# crz7shld.net
KiCad netlist of a schematic drawn in EAGLE
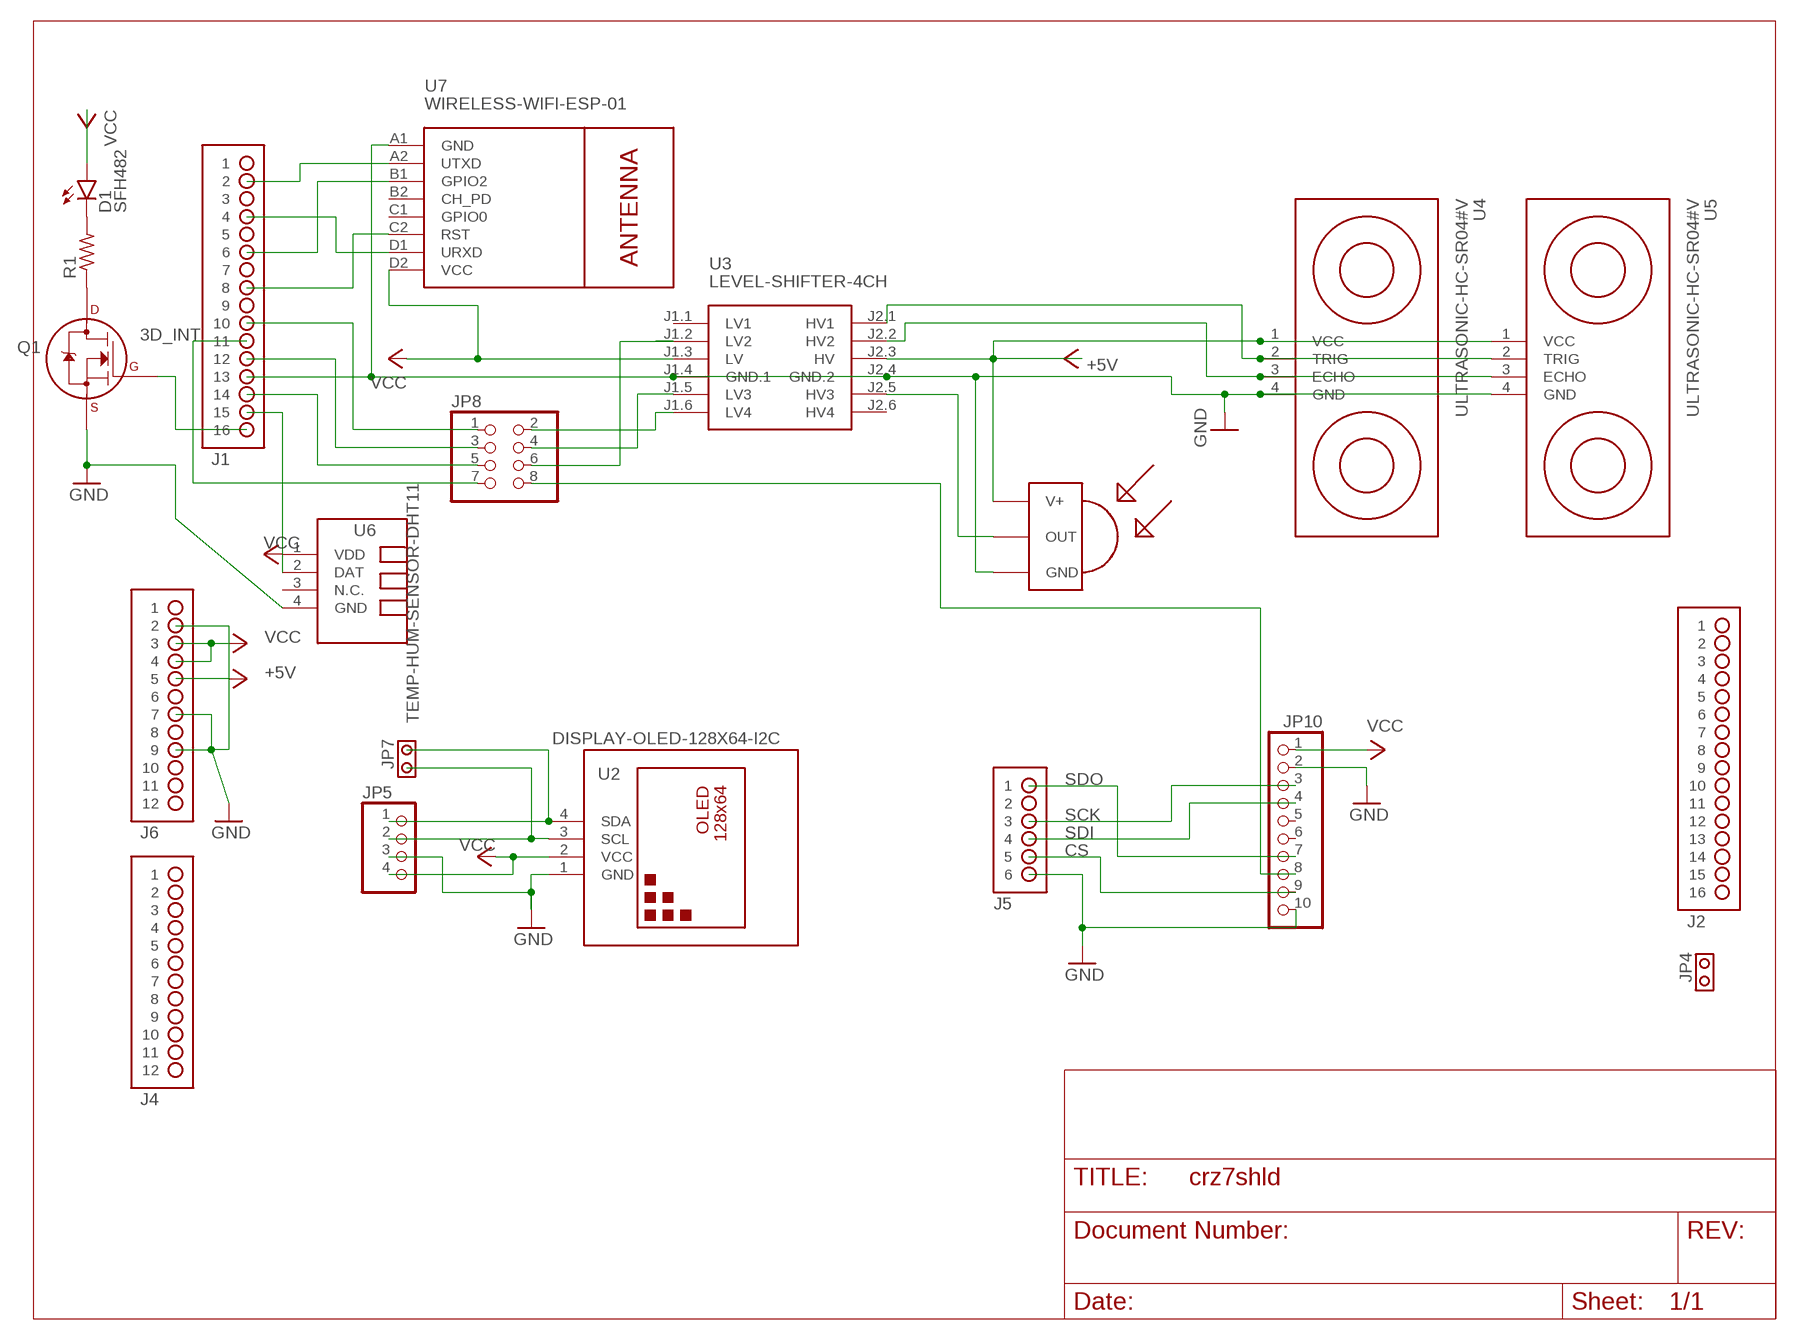
[diagram p0: schematic, sheet 1]

(export (version "E")
  (design (tool "Eeschema 10.0.6"))
  (components
    (comp (ref "D1")
      (value "SFH482")
      (footprint "eagle-import:SFH482")
      (libsource (lib "eagle-import") (part "SFH482"))
    )
    (comp (ref "J1")
      (value "HDR-2X8")
      (footprint "eagle-import:HDR-2X8")
      (libsource (lib "eagle-import") (part "HDR-2X8"))
    )
    (comp (ref "J2")
      (value "HDR-2X8")
      (footprint "eagle-import:HDR-2X8")
      (libsource (lib "eagle-import") (part "HDR-2X8"))
    )
    (comp (ref "J4")
      (value "HDR-2X6")
      (footprint "eagle-import:HDR-2X6")
      (libsource (lib "eagle-import") (part "HDR-2X6"))
    )
    (comp (ref "J5")
      (value "HDR-2X3")
      (footprint "eagle-import:HDR-2X3")
      (libsource (lib "eagle-import") (part "HDR-2X3"))
    )
    (comp (ref "J6")
      (value "HDR-2X6")
      (footprint "eagle-import:HDR-2X6")
      (libsource (lib "eagle-import") (part "HDR-2X6"))
    )
    (comp (ref "JP4")
      (value "JPR-1X2")
      (footprint "eagle-import:JPR-1X2")
      (libsource (lib "eagle-import") (part "JPR-1X2"))
    )
    (comp (ref "JP5")
      (value "PINHD-1X4")
      (footprint "eagle-import:1X04")
      (libsource (lib "eagle-import") (part "PINHD-1X4"))
    )
    (comp (ref "JP7")
      (value "JPR-1X2")
      (footprint "eagle-import:JPR-1X2")
      (libsource (lib "eagle-import") (part "JPR-1X2"))
    )
    (comp (ref "JP8")
      (value "PINHD-2X4")
      (footprint "eagle-import:2X04")
      (libsource (lib "eagle-import") (part "PINHD-2X4"))
    )
    (comp (ref "JP10")
      (value "PINHD-1X10")
      (footprint "eagle-import:1X10")
      (libsource (lib "eagle-import") (part "PINHD-1X10"))
    )
    (comp (ref "Q1")
      (value "2N7000_TO92")
      (footprint "eagle-import:TO-92")
      (libsource (lib "eagle-import") (part "2N700_TO920"))
    )
    (comp (ref "R1")
      (value "R-US_0204/5")
      (footprint "eagle-import:0204_5")
      (libsource (lib "eagle-import") (part "R-US_0204/5"))
    )
    (comp (ref "U1")
      (value "TSOP1833")
      (footprint "eagle-import:TSOP18XX")
      (libsource (lib "eagle-import") (part "TSOP1833"))
    )
    (comp (ref "U2")
      (value "DISPLAY-OLED-128X64-I2C")
      (footprint "eagle-import:DISPLAY-OLED-128X64-I2C")
      (libsource (lib "eagle-import") (part "DISPLAY-OLED-128X64-I2C"))
    )
    (comp (ref "U3")
      (value "LEVEL-SHIFTER-4CH")
      (footprint "eagle-import:LEVEL-SHIFTER-4CH")
      (libsource (lib "eagle-import") (part "LEVEL-SHIFTER-4CH"))
    )
    (comp (ref "U4")
      (value "ULTRASONIC-HC-SR04#V")
      (footprint "eagle-import:ULTRASONIC-HC-SR04#V")
      (libsource (lib "eagle-import") (part "ULTRASONIC-HC-SR04#V"))
    )
    (comp (ref "U5")
      (value "ULTRASONIC-HC-SR04#V")
      (footprint "eagle-import:ULTRASONIC-HC-SR04#V")
      (libsource (lib "eagle-import") (part "ULTRASONIC-HC-SR04#V"))
    )
    (comp (ref "U6")
      (value "TEMP-HUM-SENSOR-DHT11")
      (footprint "eagle-import:TEMP-HUM-SENSOR-DHT11")
      (libsource (lib "eagle-import") (part "TEMP-HUM-SENSOR-DHT11"))
    )
    (comp (ref "U7")
      (value "WIRELESS-WIFI-ESP-01")
      (footprint "eagle-import:WIRELESS-WIFI-ESP-01")
      (libsource (lib "eagle-import") (part "WIRELESS-WIFI-ESP-01"))
    )
  )
  (nets
    (net (code "1") (name "+5V") (class "Default")
      (node (ref "J6") (pin "5") (pinfunction "5_5") (pintype "passive"))
      (node (ref "U1") (pin "VCC") (pinfunction "V+_VCC") (pintype "bidirectional"))
      (node (ref "U3") (pin "J2.3") (pinfunction "HV_J2.3") (pintype "power_in"))
      (node (ref "U4") (pin "1") (pinfunction "VCC_1") (pintype "power_in"))
      (node (ref "U5") (pin "1") (pinfunction "VCC_1") (pintype "power_in"))
    )
    (net (code "2") (name "/3D_INT") (class "Default")
      (node (ref "J1") (pin "11") (pinfunction "11_11") (pintype "passive"))
      (node (ref "JP8") (pin "7") (pinfunction "7_7") (pintype "passive"))
    )
    (net (code "3") (name "/CS") (class "Default")
      (node (ref "J5") (pin "5") (pinfunction "5_5") (pintype "passive"))
      (node (ref "JP10") (pin "9") (pinfunction "9_9") (pintype "passive"))
    )
    (net (code "4") (name "/SCK") (class "Default")
      (node (ref "J5") (pin "3") (pinfunction "3_3") (pintype "passive"))
      (node (ref "JP10") (pin "3") (pinfunction "3_3") (pintype "passive"))
    )
    (net (code "5") (name "/SDI") (class "Default")
      (node (ref "J5") (pin "4") (pinfunction "4_4") (pintype "passive"))
      (node (ref "JP10") (pin "4") (pinfunction "4_4") (pintype "passive"))
    )
    (net (code "6") (name "/SDO") (class "Default")
      (node (ref "J5") (pin "1") (pinfunction "1_1") (pintype "passive"))
      (node (ref "JP10") (pin "7") (pinfunction "7_7") (pintype "passive"))
    )
    (net (code "7") (name "GND") (class "Default")
      (node (ref "J1") (pin "13") (pinfunction "13_13") (pintype "passive"))
      (node (ref "J5") (pin "6") (pinfunction "6_6") (pintype "passive"))
      (node (ref "J6") (pin "2") (pinfunction "2_2") (pintype "passive"))
      (node (ref "J6") (pin "7") (pinfunction "7_7") (pintype "passive"))
      (node (ref "J6") (pin "9") (pinfunction "9_9") (pintype "passive"))
      (node (ref "JP10") (pin "10") (pinfunction "10_10") (pintype "passive"))
      (node (ref "JP10") (pin "2") (pinfunction "2_2") (pintype "passive"))
      (node (ref "JP5") (pin "3") (pinfunction "3_3") (pintype "passive"))
      (node (ref "Q1") (pin "1") (pinfunction "S_1") (pintype "bidirectional"))
      (node (ref "U1") (pin "GND") (pinfunction "GND_GND") (pintype "bidirectional"))
      (node (ref "U2") (pin "1") (pinfunction "GND_1") (pintype "power_in"))
      (node (ref "U3") (pin "J1.4") (pinfunction "GND.1_J1.4") (pintype "power_in"))
      (node (ref "U3") (pin "J2.4") (pinfunction "GND.2_J2.4") (pintype "power_in"))
      (node (ref "U4") (pin "4") (pinfunction "GND_4") (pintype "power_in"))
      (node (ref "U5") (pin "4") (pinfunction "GND_4") (pintype "power_in"))
      (node (ref "U6") (pin "4") (pinfunction "GND_4") (pintype "power_in"))
      (node (ref "U7") (pin "A1") (pinfunction "GND_A1") (pintype "power_in"))
    )
    (net (code "8") (name "Net-(D1-C)") (class "Default")
      (node (ref "D1") (pin "K") (pinfunction "C_K") (pintype "passive"))
      (node (ref "R1") (pin "2") (pinfunction "2_2") (pintype "passive"))
    )
    (net (code "9") (name "Net-(J1-Pad10)") (class "Default")
      (node (ref "J1") (pin "10") (pinfunction "10_10") (pintype "passive"))
      (node (ref "JP8") (pin "1") (pinfunction "1_1") (pintype "passive"))
    )
    (net (code "10") (name "Net-(J1-Pad12)") (class "Default")
      (node (ref "J1") (pin "12") (pinfunction "12_12") (pintype "passive"))
      (node (ref "JP8") (pin "3") (pinfunction "3_3") (pintype "passive"))
    )
    (net (code "11") (name "Net-(J1-Pad14)") (class "Default")
      (node (ref "J1") (pin "14") (pinfunction "14_14") (pintype "passive"))
      (node (ref "JP8") (pin "5") (pinfunction "5_5") (pintype "passive"))
    )
    (net (code "12") (name "Net-(JP10-Pad8)") (class "Default")
      (node (ref "JP10") (pin "8") (pinfunction "8_8") (pintype "passive"))
      (node (ref "JP8") (pin "8") (pinfunction "8_8") (pintype "passive"))
    )
    (net (code "13") (name "Net-(Q1-D)") (class "Default")
      (node (ref "Q1") (pin "3") (pinfunction "D_3") (pintype "bidirectional"))
      (node (ref "R1") (pin "1") (pinfunction "1_1") (pintype "passive"))
    )
    (net (code "14") (name "Net-(Q1-G)") (class "Default")
      (node (ref "J1") (pin "16") (pinfunction "16_16") (pintype "passive"))
      (node (ref "Q1") (pin "2") (pinfunction "G_2") (pintype "tri_state"))
    )
    (net (code "15") (name "Net-(U2-SCL)") (class "Default")
      (node (ref "JP5") (pin "2") (pinfunction "2_2") (pintype "passive"))
      (node (ref "JP7") (pin "1") (pinfunction "1_1") (pintype "passive"))
      (node (ref "U2") (pin "3") (pinfunction "SCL_3") (pintype "bidirectional"))
    )
    (net (code "16") (name "Net-(U2-SDA)") (class "Default")
      (node (ref "JP5") (pin "1") (pinfunction "1_1") (pintype "passive"))
      (node (ref "JP7") (pin "2") (pinfunction "2_2") (pintype "passive"))
      (node (ref "U2") (pin "4") (pinfunction "SDA_4") (pintype "bidirectional"))
    )
    (net (code "17") (name "Net-(U3-HV1)") (class "Default")
      (node (ref "U3") (pin "J2.1") (pinfunction "HV1_J2.1") (pintype "bidirectional"))
      (node (ref "U4") (pin "2") (pinfunction "TRIG_2") (pintype "input"))
      (node (ref "U5") (pin "2") (pinfunction "TRIG_2") (pintype "input"))
    )
    (net (code "18") (name "Net-(U3-HV2)") (class "Default")
      (node (ref "U3") (pin "J2.2") (pinfunction "HV2_J2.2") (pintype "bidirectional"))
      (node (ref "U4") (pin "3") (pinfunction "ECHO_3") (pintype "output"))
      (node (ref "U5") (pin "3") (pinfunction "ECHO_3") (pintype "output"))
    )
    (net (code "19") (name "Net-(U3-HV3)") (class "Default")
      (node (ref "U1") (pin "OUT") (pinfunction "OUT_OUT") (pintype "bidirectional"))
      (node (ref "U3") (pin "J2.5") (pinfunction "HV3_J2.5") (pintype "bidirectional"))
    )
    (net (code "20") (name "Net-(U3-LV2)") (class "Default")
      (node (ref "JP8") (pin "6") (pinfunction "6_6") (pintype "passive"))
      (node (ref "U3") (pin "J1.2") (pinfunction "LV2_J1.2") (pintype "bidirectional"))
    )
    (net (code "21") (name "Net-(U3-LV3)") (class "Default")
      (node (ref "JP8") (pin "4") (pinfunction "4_4") (pintype "passive"))
      (node (ref "U3") (pin "J1.5") (pinfunction "LV3_J1.5") (pintype "bidirectional"))
    )
    (net (code "22") (name "Net-(U3-LV4)") (class "Default")
      (node (ref "JP8") (pin "2") (pinfunction "2_2") (pintype "passive"))
      (node (ref "U3") (pin "J1.6") (pinfunction "LV4_J1.6") (pintype "bidirectional"))
    )
    (net (code "23") (name "Net-(U6-DAT)") (class "Default")
      (node (ref "J1") (pin "15") (pinfunction "15_15") (pintype "passive"))
      (node (ref "U6") (pin "2") (pinfunction "DAT_2") (pintype "bidirectional"))
    )
    (net (code "24") (name "Net-(U7-GPIO2)") (class "Default")
      (node (ref "J1") (pin "6") (pinfunction "6_6") (pintype "passive"))
      (node (ref "U7") (pin "B1") (pinfunction "GPIO2_B1") (pintype "bidirectional"))
    )
    (net (code "25") (name "Net-(U7-RST)") (class "Default")
      (node (ref "J1") (pin "8") (pinfunction "8_8") (pintype "passive"))
      (node (ref "U7") (pin "C2") (pinfunction "RST_C2") (pintype "bidirectional"))
    )
    (net (code "26") (name "Net-(U7-URXD)") (class "Default")
      (node (ref "J1") (pin "4") (pinfunction "4_4") (pintype "passive"))
      (node (ref "U7") (pin "D1") (pinfunction "URXD_D1") (pintype "bidirectional"))
    )
    (net (code "27") (name "Net-(U7-UTXD)") (class "Default")
      (node (ref "J1") (pin "2") (pinfunction "2_2") (pintype "passive"))
      (node (ref "U7") (pin "A2") (pinfunction "UTXD_A2") (pintype "bidirectional"))
    )
    (net (code "28") (name "VCC") (class "Default")
      (node (ref "D1") (pin "A") (pinfunction "A_A") (pintype "passive"))
      (node (ref "J6") (pin "3") (pinfunction "3_3") (pintype "passive"))
      (node (ref "J6") (pin "4") (pinfunction "4_4") (pintype "passive"))
      (node (ref "JP10") (pin "1") (pinfunction "1_1") (pintype "passive"))
      (node (ref "JP5") (pin "4") (pinfunction "4_4") (pintype "passive"))
      (node (ref "U2") (pin "2") (pinfunction "VCC_2") (pintype "power_in"))
      (node (ref "U3") (pin "J1.3") (pinfunction "LV_J1.3") (pintype "power_in"))
      (node (ref "U6") (pin "1") (pinfunction "VDD_1") (pintype "power_in"))
      (node (ref "U7") (pin "D2") (pinfunction "VCC_D2") (pintype "power_in"))
    )
    (net (code "29") (name "unconnected-(J1-Pad1)") (class "Default")
      (node (ref "J1") (pin "1") (pinfunction "1_1") (pintype "passive"))
    )
    (net (code "30") (name "unconnected-(J1-Pad3)") (class "Default")
      (node (ref "J1") (pin "3") (pinfunction "3_3") (pintype "passive"))
    )
    (net (code "31") (name "unconnected-(J1-Pad5)") (class "Default")
      (node (ref "J1") (pin "5") (pinfunction "5_5") (pintype "passive"))
    )
    (net (code "32") (name "unconnected-(J1-Pad7)") (class "Default")
      (node (ref "J1") (pin "7") (pinfunction "7_7") (pintype "passive"))
    )
    (net (code "33") (name "unconnected-(J1-Pad9)") (class "Default")
      (node (ref "J1") (pin "9") (pinfunction "9_9") (pintype "passive"))
    )
    (net (code "34") (name "unconnected-(J2-Pad1)") (class "Default")
      (node (ref "J2") (pin "1") (pinfunction "1_1") (pintype "passive"))
    )
    (net (code "35") (name "unconnected-(J2-Pad2)") (class "Default")
      (node (ref "J2") (pin "2") (pinfunction "2_2") (pintype "passive"))
    )
    (net (code "36") (name "unconnected-(J2-Pad3)") (class "Default")
      (node (ref "J2") (pin "3") (pinfunction "3_3") (pintype "passive"))
    )
    (net (code "37") (name "unconnected-(J2-Pad4)") (class "Default")
      (node (ref "J2") (pin "4") (pinfunction "4_4") (pintype "passive"))
    )
    (net (code "38") (name "unconnected-(J2-Pad5)") (class "Default")
      (node (ref "J2") (pin "5") (pinfunction "5_5") (pintype "passive"))
    )
    (net (code "39") (name "unconnected-(J2-Pad6)") (class "Default")
      (node (ref "J2") (pin "6") (pinfunction "6_6") (pintype "passive"))
    )
    (net (code "40") (name "unconnected-(J2-Pad7)") (class "Default")
      (node (ref "J2") (pin "7") (pinfunction "7_7") (pintype "passive"))
    )
    (net (code "41") (name "unconnected-(J2-Pad8)") (class "Default")
      (node (ref "J2") (pin "8") (pinfunction "8_8") (pintype "passive"))
    )
    (net (code "42") (name "unconnected-(J2-Pad9)") (class "Default")
      (node (ref "J2") (pin "9") (pinfunction "9_9") (pintype "passive"))
    )
    (net (code "43") (name "unconnected-(J2-Pad10)") (class "Default")
      (node (ref "J2") (pin "10") (pinfunction "10_10") (pintype "passive"))
    )
    (net (code "44") (name "unconnected-(J2-Pad11)") (class "Default")
      (node (ref "J2") (pin "11") (pinfunction "11_11") (pintype "passive"))
    )
    (net (code "45") (name "unconnected-(J2-Pad12)") (class "Default")
      (node (ref "J2") (pin "12") (pinfunction "12_12") (pintype "passive"))
    )
    (net (code "46") (name "unconnected-(J2-Pad13)") (class "Default")
      (node (ref "J2") (pin "13") (pinfunction "13_13") (pintype "passive"))
    )
    (net (code "47") (name "unconnected-(J2-Pad14)") (class "Default")
      (node (ref "J2") (pin "14") (pinfunction "14_14") (pintype "passive"))
    )
    (net (code "48") (name "unconnected-(J2-Pad15)") (class "Default")
      (node (ref "J2") (pin "15") (pinfunction "15_15") (pintype "passive"))
    )
    (net (code "49") (name "unconnected-(J2-Pad16)") (class "Default")
      (node (ref "J2") (pin "16") (pinfunction "16_16") (pintype "passive"))
    )
    (net (code "50") (name "unconnected-(J4-Pad1)") (class "Default")
      (node (ref "J4") (pin "1") (pinfunction "1_1") (pintype "passive"))
    )
    (net (code "51") (name "unconnected-(J4-Pad2)") (class "Default")
      (node (ref "J4") (pin "2") (pinfunction "2_2") (pintype "passive"))
    )
    (net (code "52") (name "unconnected-(J4-Pad3)") (class "Default")
      (node (ref "J4") (pin "3") (pinfunction "3_3") (pintype "passive"))
    )
    (net (code "53") (name "unconnected-(J4-Pad4)") (class "Default")
      (node (ref "J4") (pin "4") (pinfunction "4_4") (pintype "passive"))
    )
    (net (code "54") (name "unconnected-(J4-Pad5)") (class "Default")
      (node (ref "J4") (pin "5") (pinfunction "5_5") (pintype "passive"))
    )
    (net (code "55") (name "unconnected-(J4-Pad6)") (class "Default")
      (node (ref "J4") (pin "6") (pinfunction "6_6") (pintype "passive"))
    )
    (net (code "56") (name "unconnected-(J4-Pad7)") (class "Default")
      (node (ref "J4") (pin "7") (pinfunction "7_7") (pintype "passive"))
    )
    (net (code "57") (name "unconnected-(J4-Pad8)") (class "Default")
      (node (ref "J4") (pin "8") (pinfunction "8_8") (pintype "passive"))
    )
    (net (code "58") (name "unconnected-(J4-Pad9)") (class "Default")
      (node (ref "J4") (pin "9") (pinfunction "9_9") (pintype "passive"))
    )
    (net (code "59") (name "unconnected-(J4-Pad10)") (class "Default")
      (node (ref "J4") (pin "10") (pinfunction "10_10") (pintype "passive"))
    )
    (net (code "60") (name "unconnected-(J4-Pad11)") (class "Default")
      (node (ref "J4") (pin "11") (pinfunction "11_11") (pintype "passive"))
    )
    (net (code "61") (name "unconnected-(J4-Pad12)") (class "Default")
      (node (ref "J4") (pin "12") (pinfunction "12_12") (pintype "passive"))
    )
    (net (code "62") (name "unconnected-(J5-Pad2)") (class "Default")
      (node (ref "J5") (pin "2") (pinfunction "2_2") (pintype "passive"))
    )
    (net (code "63") (name "unconnected-(J6-Pad1)") (class "Default")
      (node (ref "J6") (pin "1") (pinfunction "1_1") (pintype "passive"))
    )
    (net (code "64") (name "unconnected-(J6-Pad6)") (class "Default")
      (node (ref "J6") (pin "6") (pinfunction "6_6") (pintype "passive"))
    )
    (net (code "65") (name "unconnected-(J6-Pad8)") (class "Default")
      (node (ref "J6") (pin "8") (pinfunction "8_8") (pintype "passive"))
    )
    (net (code "66") (name "unconnected-(J6-Pad10)") (class "Default")
      (node (ref "J6") (pin "10") (pinfunction "10_10") (pintype "passive"))
    )
    (net (code "67") (name "unconnected-(J6-Pad11)") (class "Default")
      (node (ref "J6") (pin "11") (pinfunction "11_11") (pintype "passive"))
    )
    (net (code "68") (name "unconnected-(J6-Pad12)") (class "Default")
      (node (ref "J6") (pin "12") (pinfunction "12_12") (pintype "passive"))
    )
    (net (code "69") (name "unconnected-(JP4-Pad1)") (class "Default")
      (node (ref "JP4") (pin "1") (pinfunction "1_1") (pintype "passive"))
    )
    (net (code "70") (name "unconnected-(JP4-Pad2)") (class "Default")
      (node (ref "JP4") (pin "2") (pinfunction "2_2") (pintype "passive"))
    )
    (net (code "71") (name "unconnected-(JP10-Pad5)") (class "Default")
      (node (ref "JP10") (pin "5") (pinfunction "5_5") (pintype "passive"))
    )
    (net (code "72") (name "unconnected-(JP10-Pad6)") (class "Default")
      (node (ref "JP10") (pin "6") (pinfunction "6_6") (pintype "passive"))
    )
    (net (code "73") (name "unconnected-(U3-HV4-PadJ2.6)") (class "Default")
      (node (ref "U3") (pin "J2.6") (pinfunction "HV4_J2.6") (pintype "bidirectional"))
    )
    (net (code "74") (name "unconnected-(U3-LV1-PadJ1.1)") (class "Default")
      (node (ref "U3") (pin "J1.1") (pinfunction "LV1_J1.1") (pintype "bidirectional"))
    )
    (net (code "75") (name "unconnected-(U6-N.C.-Pad3)") (class "Default")
      (node (ref "U6") (pin "3") (pinfunction "N.C._3") (pintype "passive"))
    )
    (net (code "76") (name "unconnected-(U7-CH_PD-PadB2)") (class "Default")
      (node (ref "U7") (pin "B2") (pinfunction "CH_PD_B2") (pintype "bidirectional"))
    )
    (net (code "77") (name "unconnected-(U7-GPIO0-PadC1)") (class "Default")
      (node (ref "U7") (pin "C1") (pinfunction "GPIO0_C1") (pintype "bidirectional"))
    )
  )
)
